# ir-sensor-breakout-mk-3_1.net
KiCad netlist of a schematic drawn in EAGLE
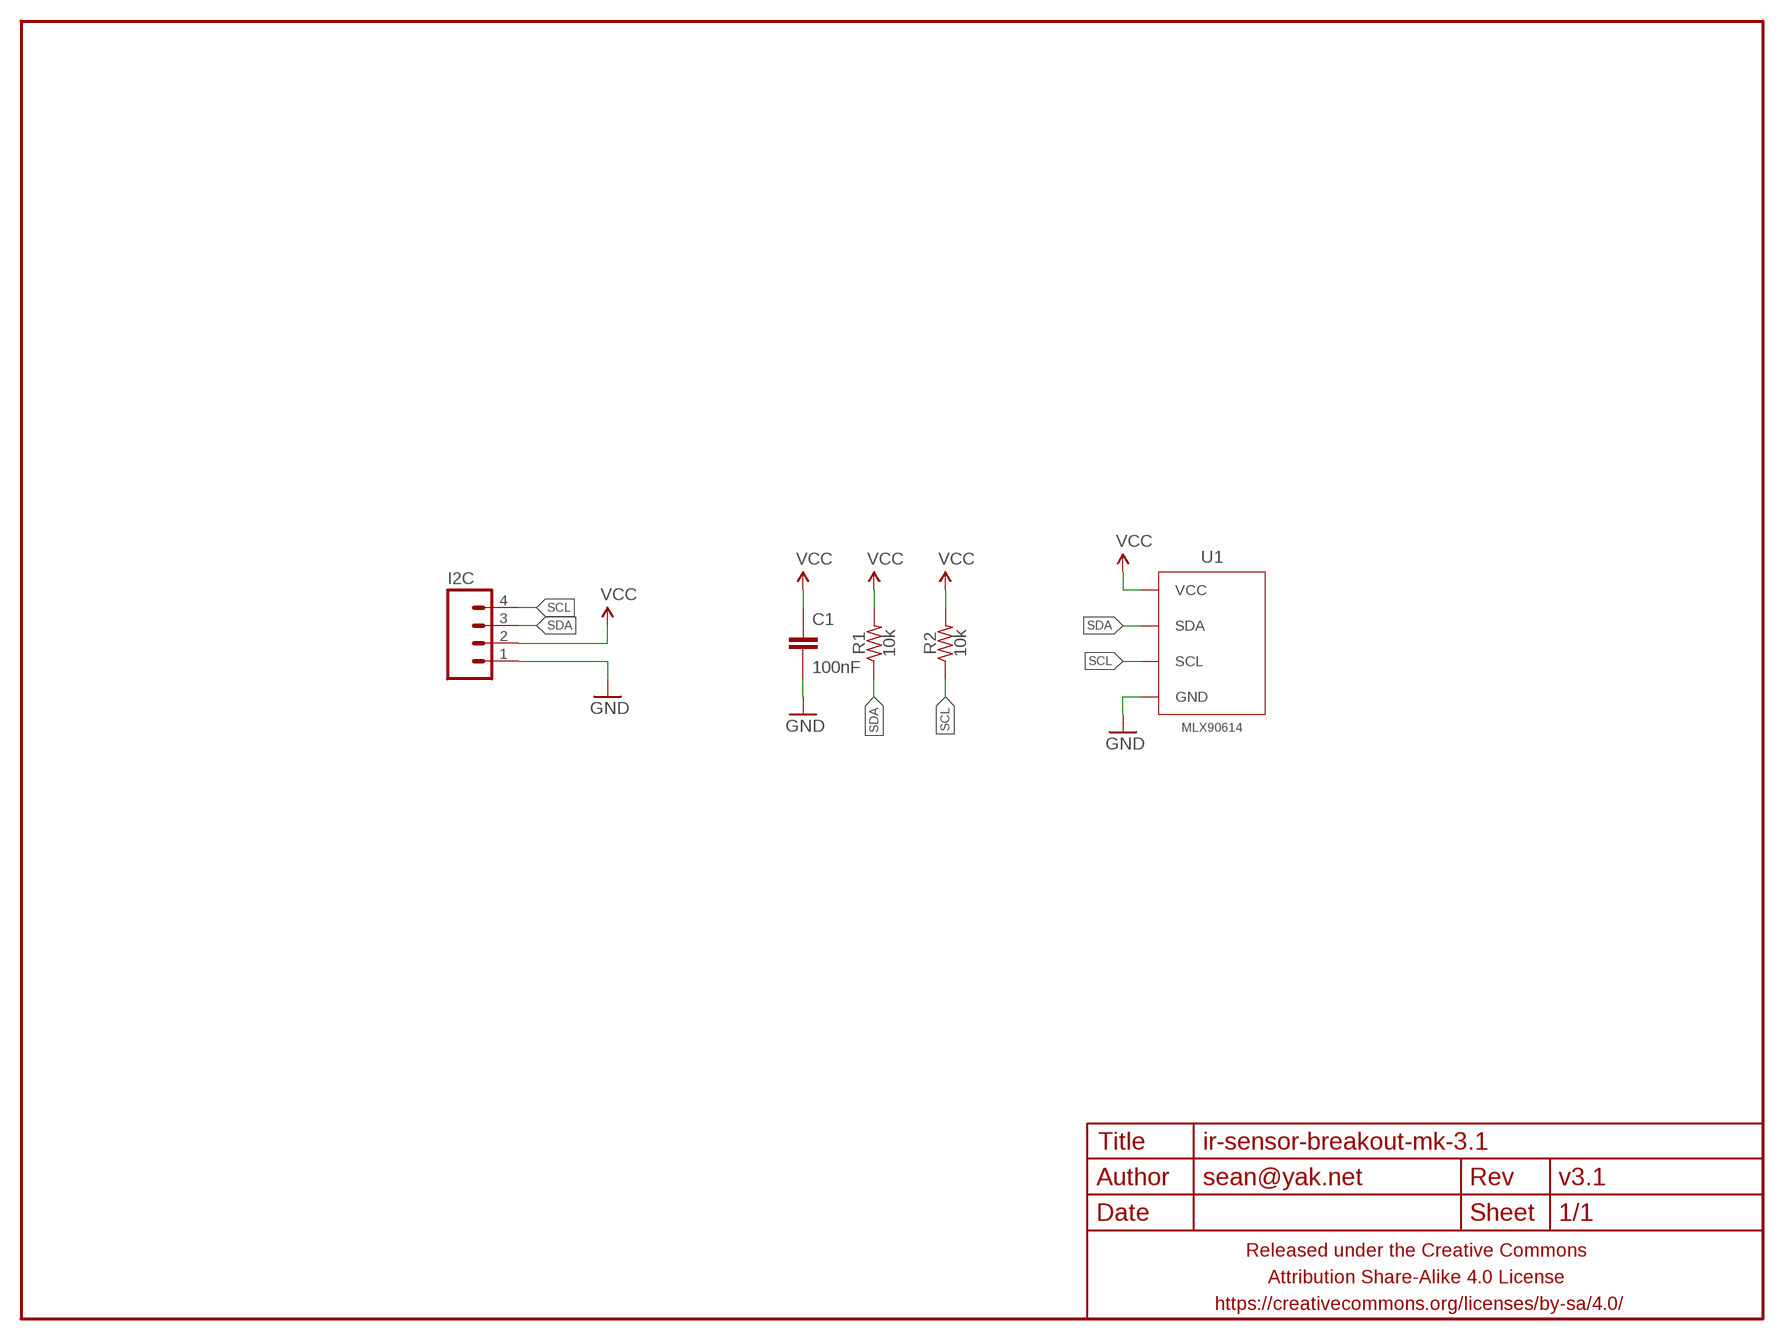
[diagram p0: schematic, sheet 1]

(export (version "E")
  (design (tool "Eeschema 10.0.6"))
  (components
    (comp (ref "C1")
      (value "100nF")
      (footprint "eagle-import:C0603")
      (libsource (lib "eagle-import") (part "CAPACITOR-CERAMICC0603"))
    )
    (comp (ref "FRAME1")
      (value "FRAME-LETTERNO_PACKAGE")
      (footprint "eagle-import:DUMMY")
      (fields (field (name "DESIGNER") "sean@yak.net") (field (name "VERSION") "v3.1"))
      (libsource (lib "eagle-import") (part "FRAME-LETTERNO_PACKAGE"))
    )
    (comp (ref "I2C")
      (value "M04JST-PTH-VERT")
      (footprint "eagle-import:JST-4-PH-VERT-PTH")
      (libsource (lib "eagle-import") (part "M04JST-PTH-VERT"))
    )
    (comp (ref "R1")
      (value "10k")
      (footprint "eagle-import:R0603")
      (libsource (lib "eagle-import") (part "RESISTORR0603"))
    )
    (comp (ref "R2")
      (value "10k")
      (footprint "eagle-import:R0603")
      (libsource (lib "eagle-import") (part "RESISTORR0603"))
    )
    (comp (ref "U1")
      (value "MLX90614")
      (footprint "eagle-import:TO-39-4")
      (libsource (lib "eagle-import") (part "MLX906145V-PTH"))
    )
  )
  (nets
    (net (code "1") (name "GND") (class "Default")
      (node (ref "C1") (pin "2") (pinfunction "2_2") (pintype "passive"))
      (node (ref "I2C") (pin "1") (pinfunction "1_1") (pintype "passive"))
      (node (ref "U1") (pin "4") (pinfunction "GND_4") (pintype "bidirectional"))
    )
    (net (code "2") (name "SCL") (class "Default")
      (node (ref "I2C") (pin "4") (pinfunction "4_4") (pintype "passive"))
      (node (ref "R2") (pin "1") (pinfunction "1_1") (pintype "passive"))
      (node (ref "U1") (pin "1") (pinfunction "SCL_1") (pintype "bidirectional"))
    )
    (net (code "3") (name "SDA") (class "Default")
      (node (ref "I2C") (pin "3") (pinfunction "3_3") (pintype "passive"))
      (node (ref "R1") (pin "1") (pinfunction "1_1") (pintype "passive"))
      (node (ref "U1") (pin "2") (pinfunction "SDA_2") (pintype "bidirectional"))
    )
    (net (code "4") (name "VCC") (class "Default")
      (node (ref "C1") (pin "1") (pinfunction "1_1") (pintype "passive"))
      (node (ref "I2C") (pin "2") (pinfunction "2_2") (pintype "passive"))
      (node (ref "R1") (pin "2") (pinfunction "2_2") (pintype "passive"))
      (node (ref "R2") (pin "2") (pinfunction "2_2") (pintype "passive"))
      (node (ref "U1") (pin "3") (pinfunction "VCC_3") (pintype "bidirectional"))
    )
  )
)
